# JKF_1_0.net
KiCad netlist of a schematic drawn in EAGLE
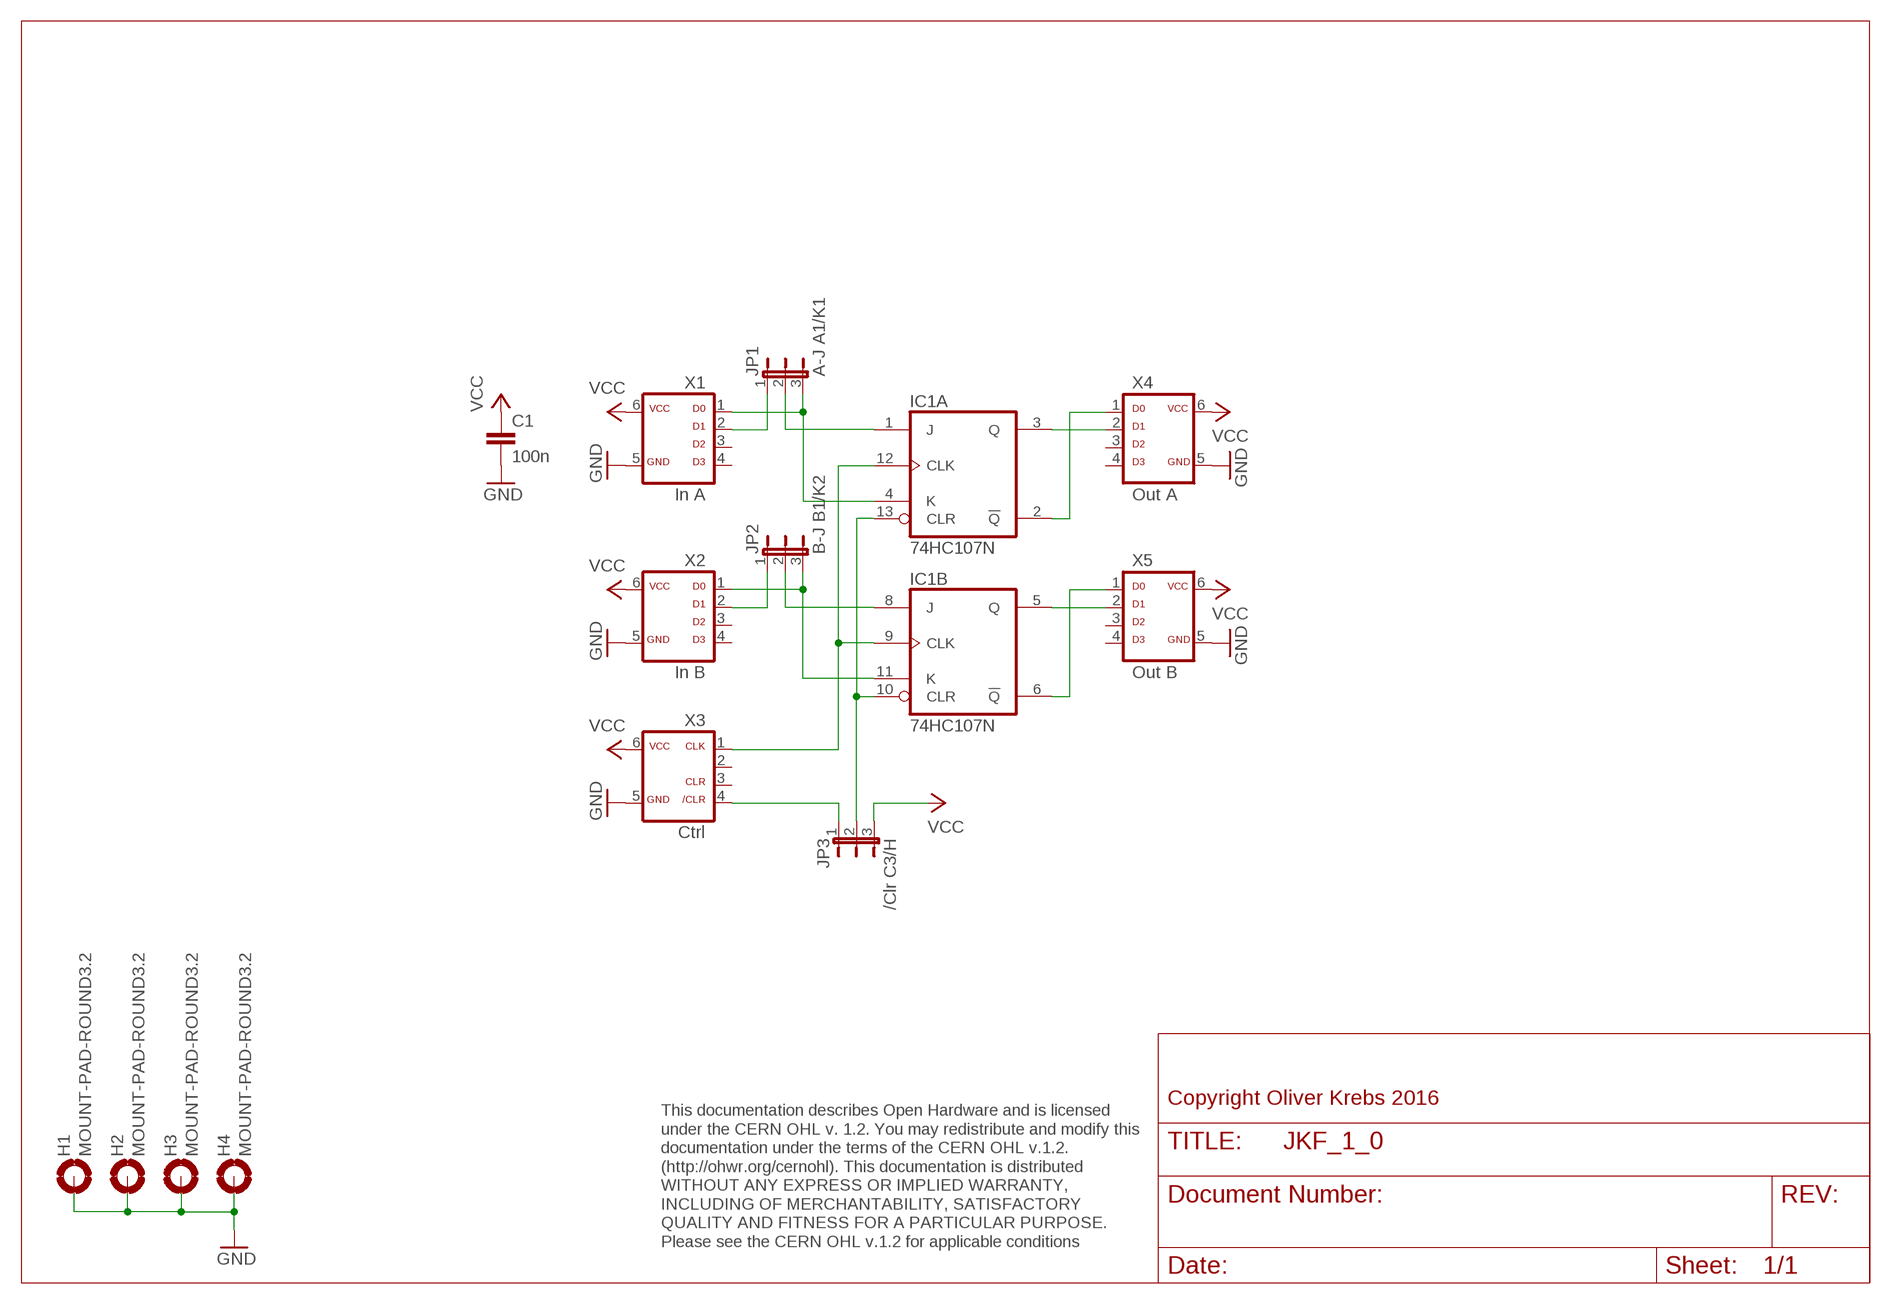
[diagram p0: schematic, sheet 1]

(export (version "E")
  (design (tool "Eeschema 10.0.6"))
  (components
    (comp (ref "C1")
      (value "100n")
      (footprint "eagle-import:C050-025X075")
      (libsource (lib "eagle-import") (part "C-EU050-025X075"))
    )
    (comp (ref "H1")
      (value "MOUNT-PAD-ROUND3.2")
      (footprint "eagle-import:3,2-PAD")
      (libsource (lib "eagle-import") (part "MOUNT-PAD-ROUND3.2"))
    )
    (comp (ref "H2")
      (value "MOUNT-PAD-ROUND3.2")
      (footprint "eagle-import:3,2-PAD")
      (libsource (lib "eagle-import") (part "MOUNT-PAD-ROUND3.2"))
    )
    (comp (ref "H3")
      (value "MOUNT-PAD-ROUND3.2")
      (footprint "eagle-import:3,2-PAD")
      (libsource (lib "eagle-import") (part "MOUNT-PAD-ROUND3.2"))
    )
    (comp (ref "H4")
      (value "MOUNT-PAD-ROUND3.2")
      (footprint "eagle-import:3,2-PAD")
      (libsource (lib "eagle-import") (part "MOUNT-PAD-ROUND3.2"))
    )
    (comp (ref "IC1")
      (value "74HC107N")
      (footprint "eagle-import:DIL14")
      (libsource (lib "eagle-import") (part "74107NHC"))
    )
    (comp (ref "JP1")
      (value "A-J A1/K1")
      (footprint "eagle-import:JP2")
      (libsource (lib "eagle-import") (part "JP2E"))
    )
    (comp (ref "JP2")
      (value "B-J B1/K2")
      (footprint "eagle-import:JP2")
      (libsource (lib "eagle-import") (part "JP2E"))
    )
    (comp (ref "JP3")
      (value "/Clr C3/H")
      (footprint "eagle-import:JP2")
      (libsource (lib "eagle-import") (part "JP2E"))
    )
    (comp (ref "X1")
      (value "In A")
      (footprint "eagle-import:ML-6")
      (libsource (lib "eagle-import") (part "ML6D"))
    )
    (comp (ref "X2")
      (value "In B")
      (footprint "eagle-import:ML-6")
      (libsource (lib "eagle-import") (part "ML6D"))
    )
    (comp (ref "X3")
      (value "Ctrl")
      (footprint "eagle-import:ML-6")
      (libsource (lib "eagle-import") (part "ML6C"))
    )
    (comp (ref "X4")
      (value "Out A")
      (footprint "eagle-import:ML-6")
      (libsource (lib "eagle-import") (part "ML6D"))
    )
    (comp (ref "X5")
      (value "Out B")
      (footprint "eagle-import:ML-6")
      (libsource (lib "eagle-import") (part "ML6D"))
    )
  )
  (nets
    (net (code "1") (name "GND") (class "Default")
      (node (ref "C1") (pin "2") (pinfunction "2_2") (pintype "passive"))
      (node (ref "H1") (pin "B3,2") (pinfunction "MOUNT_B3,2") (pintype "passive"))
      (node (ref "H2") (pin "B3,2") (pinfunction "MOUNT_B3,2") (pintype "passive"))
      (node (ref "H3") (pin "B3,2") (pinfunction "MOUNT_B3,2") (pintype "passive"))
      (node (ref "H4") (pin "B3,2") (pinfunction "MOUNT_B3,2") (pintype "passive"))
      (node (ref "X1") (pin "5") (pinfunction "5_5") (pintype "passive"))
      (node (ref "X2") (pin "5") (pinfunction "5_5") (pintype "passive"))
      (node (ref "X3") (pin "5") (pinfunction "5_5") (pintype "passive"))
      (node (ref "X4") (pin "5") (pinfunction "5_5") (pintype "passive"))
      (node (ref "X5") (pin "5") (pinfunction "5_5") (pintype "passive"))
    )
    (net (code "2") (name "Net-(IC1A-CLK)") (class "Default")
      (node (ref "IC1") (pin "12") (pinfunction "CLK_12") (pintype "input"))
      (node (ref "IC1") (pin "9") (pinfunction "CLK_9") (pintype "input"))
      (node (ref "X3") (pin "1") (pinfunction "1_1") (pintype "passive"))
    )
    (net (code "3") (name "Net-(IC1A-CLR)") (class "Default")
      (node (ref "IC1") (pin "10") (pinfunction "CLR_10") (pintype "input"))
      (node (ref "IC1") (pin "13") (pinfunction "CLR_13") (pintype "input"))
      (node (ref "JP3") (pin "2") (pinfunction "2_2") (pintype "passive"))
    )
    (net (code "4") (name "Net-(IC1A-J)") (class "Default")
      (node (ref "IC1") (pin "1") (pinfunction "J_1") (pintype "input"))
      (node (ref "JP1") (pin "2") (pinfunction "2_2") (pintype "passive"))
    )
    (net (code "5") (name "Net-(IC1A-K)") (class "Default")
      (node (ref "IC1") (pin "4") (pinfunction "K_4") (pintype "input"))
      (node (ref "JP1") (pin "3") (pinfunction "3_3") (pintype "passive"))
      (node (ref "X1") (pin "1") (pinfunction "1_1") (pintype "passive"))
    )
    (net (code "6") (name "Net-(IC1A-Q)") (class "Default")
      (node (ref "IC1") (pin "3") (pinfunction "Q_3") (pintype "output"))
      (node (ref "X4") (pin "2") (pinfunction "2_2") (pintype "passive"))
    )
    (net (code "7") (name "Net-(IC1A-~{Q})") (class "Default")
      (node (ref "IC1") (pin "2") (pinfunction "~{Q}_2") (pintype "output"))
      (node (ref "X4") (pin "1") (pinfunction "1_1") (pintype "passive"))
    )
    (net (code "8") (name "Net-(IC1B-J)") (class "Default")
      (node (ref "IC1") (pin "8") (pinfunction "J_8") (pintype "input"))
      (node (ref "JP2") (pin "2") (pinfunction "2_2") (pintype "passive"))
    )
    (net (code "9") (name "Net-(IC1B-K)") (class "Default")
      (node (ref "IC1") (pin "11") (pinfunction "K_11") (pintype "input"))
      (node (ref "JP2") (pin "3") (pinfunction "3_3") (pintype "passive"))
      (node (ref "X2") (pin "1") (pinfunction "1_1") (pintype "passive"))
    )
    (net (code "10") (name "Net-(IC1B-Q)") (class "Default")
      (node (ref "IC1") (pin "5") (pinfunction "Q_5") (pintype "output"))
      (node (ref "X5") (pin "2") (pinfunction "2_2") (pintype "passive"))
    )
    (net (code "11") (name "Net-(IC1B-~{Q})") (class "Default")
      (node (ref "IC1") (pin "6") (pinfunction "~{Q}_6") (pintype "output"))
      (node (ref "X5") (pin "1") (pinfunction "1_1") (pintype "passive"))
    )
    (net (code "12") (name "Net-(JP1-Pad1)") (class "Default")
      (node (ref "JP1") (pin "1") (pinfunction "1_1") (pintype "passive"))
      (node (ref "X1") (pin "2") (pinfunction "2_2") (pintype "passive"))
    )
    (net (code "13") (name "Net-(JP2-Pad1)") (class "Default")
      (node (ref "JP2") (pin "1") (pinfunction "1_1") (pintype "passive"))
      (node (ref "X2") (pin "2") (pinfunction "2_2") (pintype "passive"))
    )
    (net (code "14") (name "Net-(JP3-Pad1)") (class "Default")
      (node (ref "JP3") (pin "1") (pinfunction "1_1") (pintype "passive"))
      (node (ref "X3") (pin "4") (pinfunction "4_4") (pintype "passive"))
    )
    (net (code "15") (name "VCC") (class "Default")
      (node (ref "C1") (pin "1") (pinfunction "1_1") (pintype "passive"))
      (node (ref "JP3") (pin "3") (pinfunction "3_3") (pintype "passive"))
      (node (ref "X1") (pin "6") (pinfunction "6_6") (pintype "passive"))
      (node (ref "X2") (pin "6") (pinfunction "6_6") (pintype "passive"))
      (node (ref "X3") (pin "6") (pinfunction "6_6") (pintype "passive"))
      (node (ref "X4") (pin "6") (pinfunction "6_6") (pintype "passive"))
      (node (ref "X5") (pin "6") (pinfunction "6_6") (pintype "passive"))
    )
    (net (code "16") (name "unconnected-(X1-Pad3)") (class "Default")
      (node (ref "X1") (pin "3") (pinfunction "3_3") (pintype "passive"))
    )
    (net (code "17") (name "unconnected-(X1-Pad4)") (class "Default")
      (node (ref "X1") (pin "4") (pinfunction "4_4") (pintype "passive"))
    )
    (net (code "18") (name "unconnected-(X2-Pad3)") (class "Default")
      (node (ref "X2") (pin "3") (pinfunction "3_3") (pintype "passive"))
    )
    (net (code "19") (name "unconnected-(X2-Pad4)") (class "Default")
      (node (ref "X2") (pin "4") (pinfunction "4_4") (pintype "passive"))
    )
    (net (code "20") (name "unconnected-(X3-Pad2)") (class "Default")
      (node (ref "X3") (pin "2") (pinfunction "2_2") (pintype "passive"))
    )
    (net (code "21") (name "unconnected-(X3-Pad3)") (class "Default")
      (node (ref "X3") (pin "3") (pinfunction "3_3") (pintype "passive"))
    )
    (net (code "22") (name "unconnected-(X4-Pad3)") (class "Default")
      (node (ref "X4") (pin "3") (pinfunction "3_3") (pintype "passive"))
    )
    (net (code "23") (name "unconnected-(X4-Pad4)") (class "Default")
      (node (ref "X4") (pin "4") (pinfunction "4_4") (pintype "passive"))
    )
    (net (code "24") (name "unconnected-(X5-Pad3)") (class "Default")
      (node (ref "X5") (pin "3") (pinfunction "3_3") (pintype "passive"))
    )
    (net (code "25") (name "unconnected-(X5-Pad4)") (class "Default")
      (node (ref "X5") (pin "4") (pinfunction "4_4") (pintype "passive"))
    )
  )
)
